# 5ChannelStepperDriver.net
KiCad netlist of a schematic drawn in EAGLE
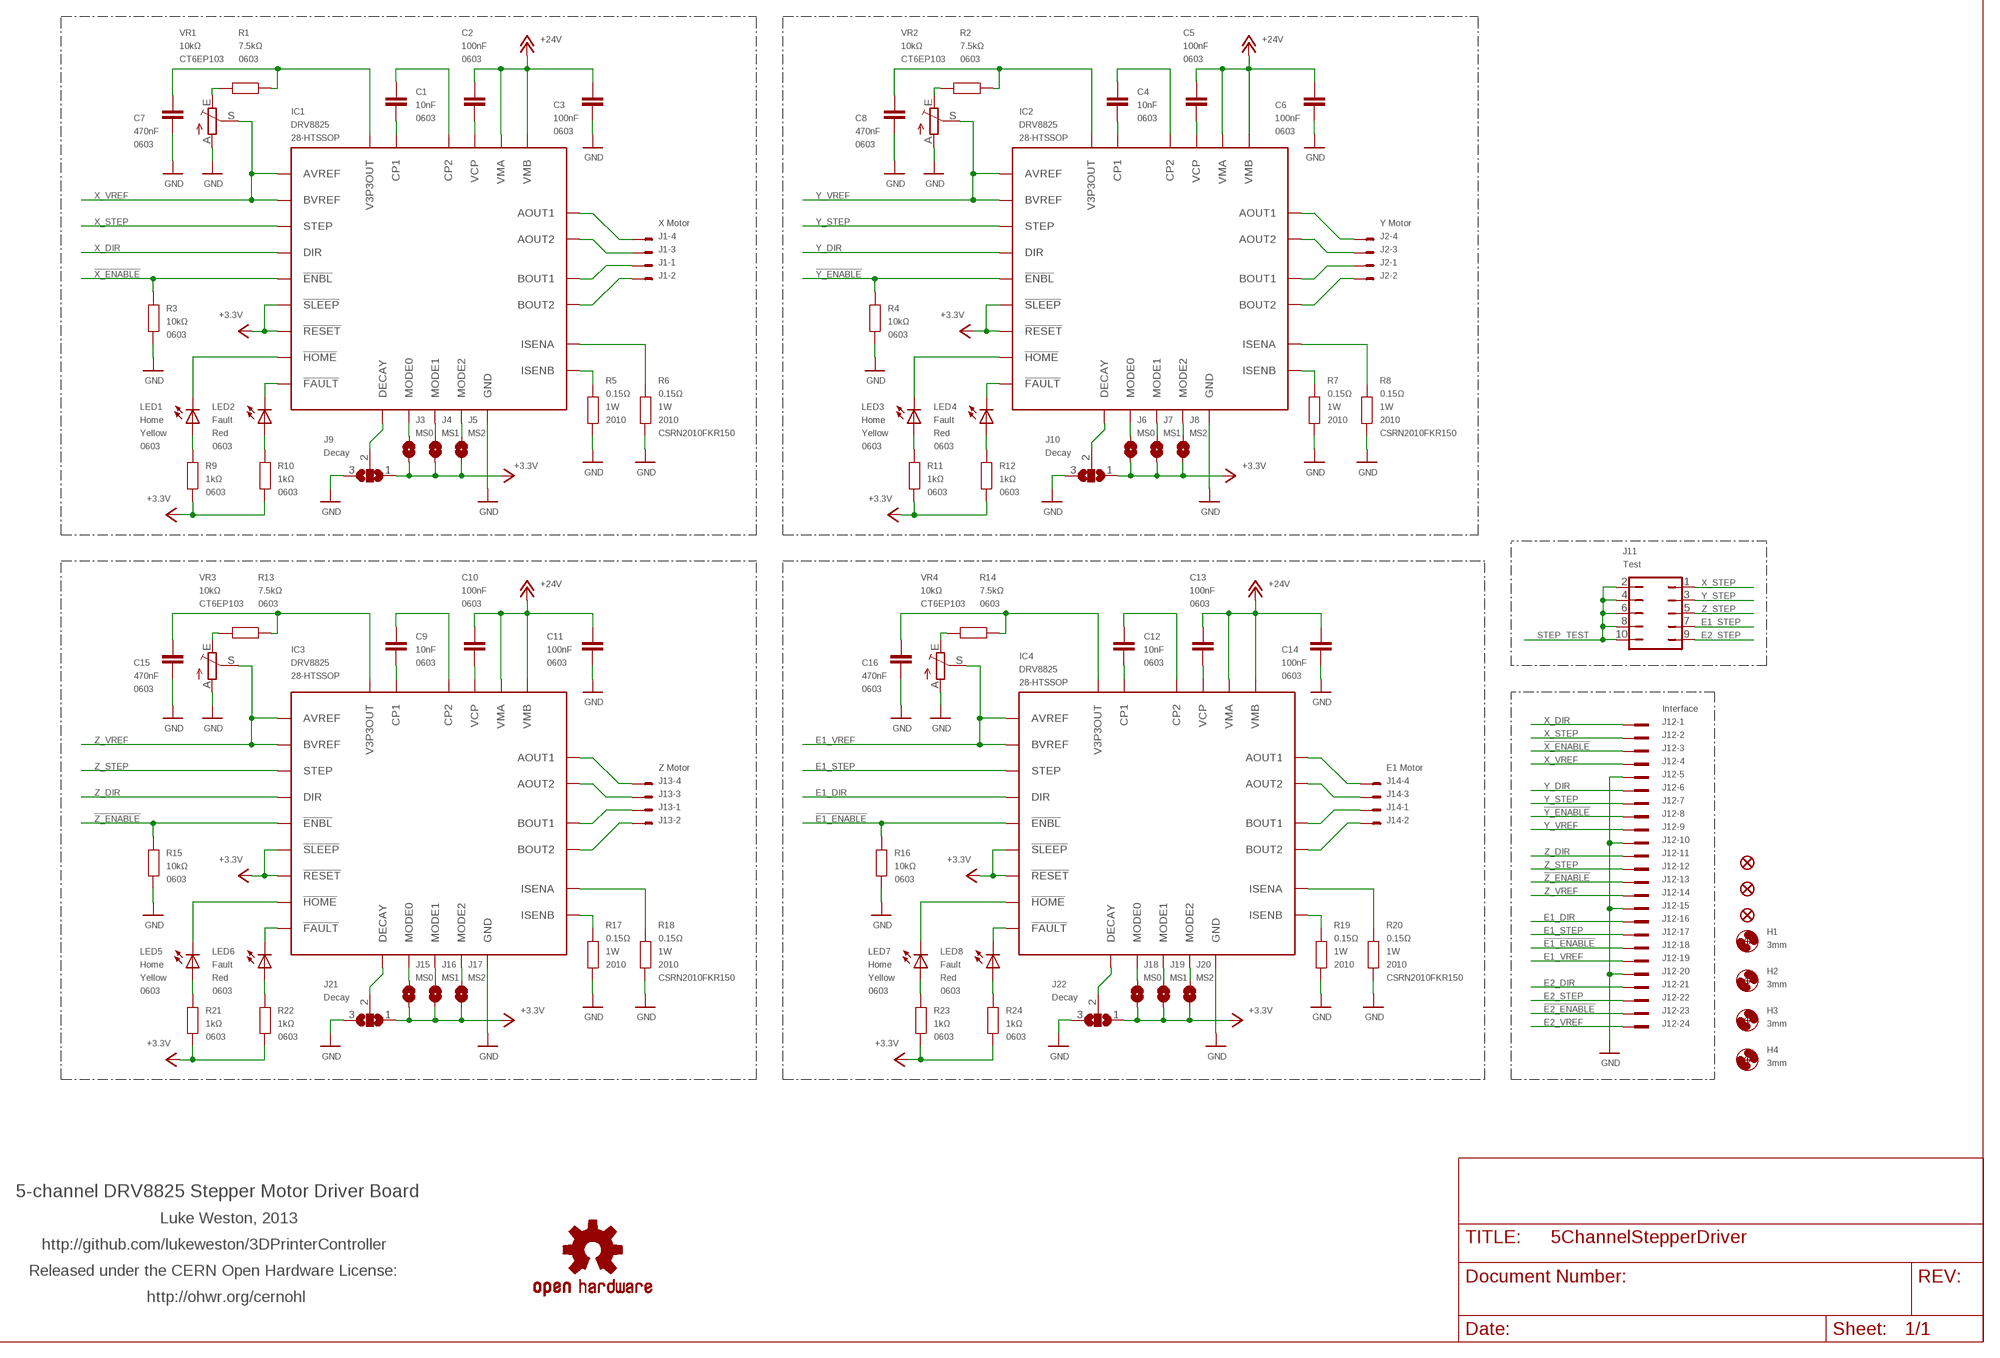
[diagram p0: schematic, sheet 1, part 1 of 3]
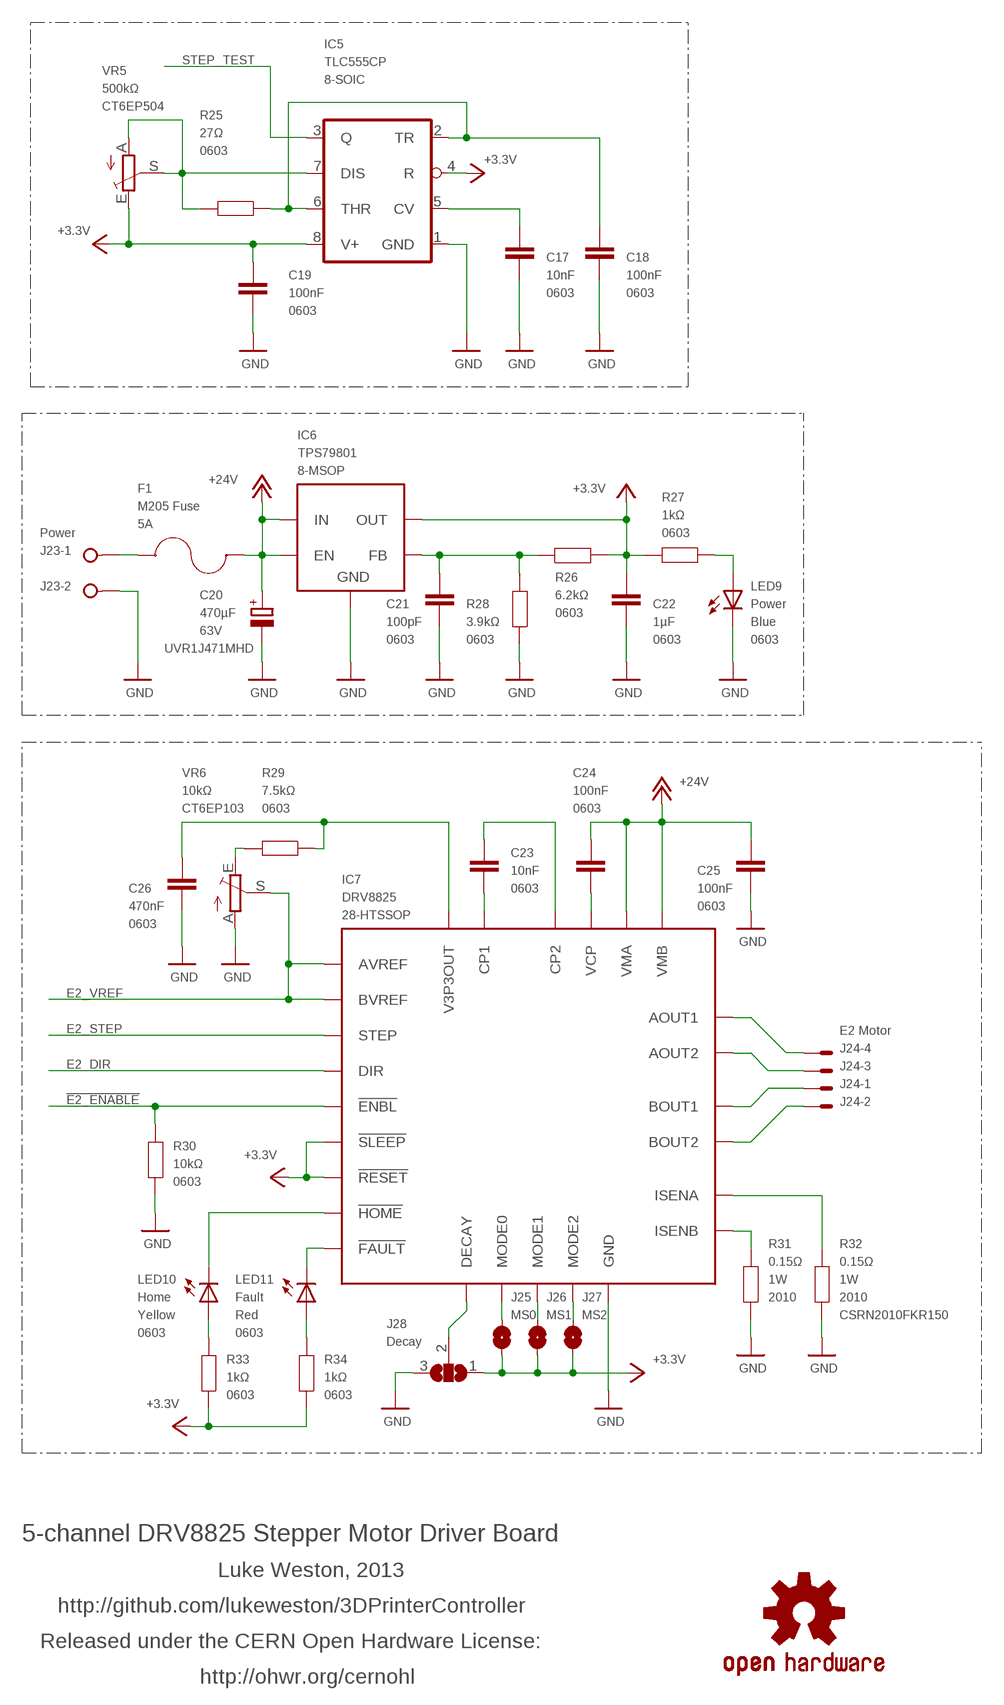
[diagram p1: schematic, sheet 1, part 2 of 3]
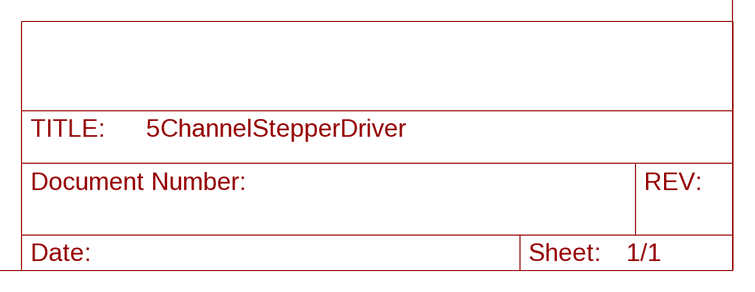
[diagram p2: schematic, sheet 1, part 3 of 3]

(export (version "E")
  (design (tool "Eeschema 10.0.6"))
  (components
    (comp (ref "C1")
      (value "10nF")
      (footprint "eagle-import:0603")
      (fields (field (name "PACKAGE") "0603"))
      (libsource (lib "eagle-import") (part "CAP0603"))
    )
    (comp (ref "C2")
      (value "100nF")
      (footprint "eagle-import:0603")
      (fields (field (name "PACKAGE") "0603"))
      (libsource (lib "eagle-import") (part "CAP0603"))
    )
    (comp (ref "C3")
      (value "100nF")
      (footprint "eagle-import:0603")
      (fields (field (name "PACKAGE") "0603"))
      (libsource (lib "eagle-import") (part "CAP0603"))
    )
    (comp (ref "C4")
      (value "10nF")
      (footprint "eagle-import:0603")
      (fields (field (name "PACKAGE") "0603"))
      (libsource (lib "eagle-import") (part "CAP0603"))
    )
    (comp (ref "C5")
      (value "100nF")
      (footprint "eagle-import:0603")
      (fields (field (name "PACKAGE") "0603"))
      (libsource (lib "eagle-import") (part "CAP0603"))
    )
    (comp (ref "C6")
      (value "100nF")
      (footprint "eagle-import:0603")
      (fields (field (name "PACKAGE") "0603"))
      (libsource (lib "eagle-import") (part "CAP0603"))
    )
    (comp (ref "C7")
      (value "470nF")
      (footprint "eagle-import:0603")
      (fields (field (name "PACKAGE") "0603"))
      (libsource (lib "eagle-import") (part "CAP0603"))
    )
    (comp (ref "C8")
      (value "470nF")
      (footprint "eagle-import:0603")
      (fields (field (name "PACKAGE") "0603"))
      (libsource (lib "eagle-import") (part "CAP0603"))
    )
    (comp (ref "C9")
      (value "10nF")
      (footprint "eagle-import:0603")
      (fields (field (name "PACKAGE") "0603"))
      (libsource (lib "eagle-import") (part "CAP0603"))
    )
    (comp (ref "C10")
      (value "100nF")
      (footprint "eagle-import:0603")
      (fields (field (name "PACKAGE") "0603"))
      (libsource (lib "eagle-import") (part "CAP0603"))
    )
    (comp (ref "C11")
      (value "100nF")
      (footprint "eagle-import:0603")
      (fields (field (name "PACKAGE") "0603"))
      (libsource (lib "eagle-import") (part "CAP0603"))
    )
    (comp (ref "C12")
      (value "10nF")
      (footprint "eagle-import:0603")
      (fields (field (name "PACKAGE") "0603"))
      (libsource (lib "eagle-import") (part "CAP0603"))
    )
    (comp (ref "C13")
      (value "100nF")
      (footprint "eagle-import:0603")
      (fields (field (name "PACKAGE") "0603"))
      (libsource (lib "eagle-import") (part "CAP0603"))
    )
    (comp (ref "C14")
      (value "100nF")
      (footprint "eagle-import:0603")
      (fields (field (name "PACKAGE") "0603"))
      (libsource (lib "eagle-import") (part "CAP0603"))
    )
    (comp (ref "C15")
      (value "470nF")
      (footprint "eagle-import:0603")
      (fields (field (name "PACKAGE") "0603"))
      (libsource (lib "eagle-import") (part "CAP0603"))
    )
    (comp (ref "C16")
      (value "470nF")
      (footprint "eagle-import:0603")
      (fields (field (name "PACKAGE") "0603"))
      (libsource (lib "eagle-import") (part "CAP0603"))
    )
    (comp (ref "C17")
      (value "10nF")
      (footprint "eagle-import:0603")
      (fields (field (name "PACKAGE") "0603"))
      (libsource (lib "eagle-import") (part "CAP0603"))
    )
    (comp (ref "C18")
      (value "100nF")
      (footprint "eagle-import:0603")
      (fields (field (name "PACKAGE") "0603"))
      (libsource (lib "eagle-import") (part "CAP0603"))
    )
    (comp (ref "C19")
      (value "100nF")
      (footprint "eagle-import:0603")
      (fields (field (name "PACKAGE") "0603"))
      (libsource (lib "eagle-import") (part "CAP0603"))
    )
    (comp (ref "C20")
      (value "470µF")
      (footprint "eagle-import:E5-13")
      (fields (field (name "SKU") "UVR1J471MHD") (field (name "VOLTAGE") "63V"))
      (libsource (lib "eagle-import") (part "CPOL-EUE5-13"))
    )
    (comp (ref "C21")
      (value "100pF")
      (footprint "eagle-import:0603")
      (fields (field (name "PACKAGE") "0603"))
      (libsource (lib "eagle-import") (part "CAP0603"))
    )
    (comp (ref "C22")
      (value "1µF")
      (footprint "eagle-import:0603")
      (fields (field (name "PACKAGE") "0603"))
      (libsource (lib "eagle-import") (part "CAP0603"))
    )
    (comp (ref "C23")
      (value "10nF")
      (footprint "eagle-import:0603")
      (fields (field (name "PACKAGE") "0603"))
      (libsource (lib "eagle-import") (part "CAP0603"))
    )
    (comp (ref "C24")
      (value "100nF")
      (footprint "eagle-import:0603")
      (fields (field (name "PACKAGE") "0603"))
      (libsource (lib "eagle-import") (part "CAP0603"))
    )
    (comp (ref "C25")
      (value "100nF")
      (footprint "eagle-import:0603")
      (fields (field (name "PACKAGE") "0603"))
      (libsource (lib "eagle-import") (part "CAP0603"))
    )
    (comp (ref "C26")
      (value "470nF")
      (footprint "eagle-import:0603")
      (fields (field (name "PACKAGE") "0603"))
      (libsource (lib "eagle-import") (part "CAP0603"))
    )
    (comp (ref "F1")
      (value "M205 Fuse")
      (footprint "eagle-import:FUSECLIP-FC211")
      (fields (field (name "VALUE2") "5A"))
      (libsource (lib "eagle-import") (part "FUSE-M205"))
    )
    (comp (ref "H1")
      (value "3mm")
      (footprint "eagle-import:3,0")
      (libsource (lib "eagle-import") (part "MOUNT-HOLE3.0"))
    )
    (comp (ref "H2")
      (value "3mm")
      (footprint "eagle-import:3,0")
      (libsource (lib "eagle-import") (part "MOUNT-HOLE3.0"))
    )
    (comp (ref "H3")
      (value "3mm")
      (footprint "eagle-import:3,0")
      (libsource (lib "eagle-import") (part "MOUNT-HOLE3.0"))
    )
    (comp (ref "H4")
      (value "3mm")
      (footprint "eagle-import:3,0")
      (libsource (lib "eagle-import") (part "MOUNT-HOLE3.0"))
    )
    (comp (ref "IC1")
      (value "DRV8825")
      (footprint "eagle-import:R-PDSO-G28")
      (fields (field (name "PACKAGE") "28-HTSSOP"))
      (libsource (lib "eagle-import") (part "DRV8825"))
    )
    (comp (ref "IC2")
      (value "DRV8825")
      (footprint "eagle-import:R-PDSO-G28")
      (fields (field (name "PACKAGE") "28-HTSSOP"))
      (libsource (lib "eagle-import") (part "DRV8825"))
    )
    (comp (ref "IC3")
      (value "DRV8825")
      (footprint "eagle-import:R-PDSO-G28")
      (fields (field (name "PACKAGE") "28-HTSSOP"))
      (libsource (lib "eagle-import") (part "DRV8825"))
    )
    (comp (ref "IC4")
      (value "DRV8825")
      (footprint "eagle-import:R-PDSO-G28")
      (fields (field (name "PACKAGE") "28-HTSSOP"))
      (libsource (lib "eagle-import") (part "DRV8825"))
    )
    (comp (ref "IC5")
      (value "TLC555CP")
      (footprint "eagle-import:SO08")
      (fields (field (name "PACKAGE") "8-SOIC"))
      (libsource (lib "eagle-import") (part "555DLM"))
    )
    (comp (ref "IC6")
      (value "TPS79801")
      (footprint "eagle-import:R-PDSO-G8")
      (fields (field (name "PACKAGE") "8-MSOP"))
      (libsource (lib "eagle-import") (part "TPS79801"))
    )
    (comp (ref "IC7")
      (value "DRV8825")
      (footprint "eagle-import:R-PDSO-G28")
      (fields (field (name "PACKAGE") "28-HTSSOP"))
      (libsource (lib "eagle-import") (part "DRV8825"))
    )
    (comp (ref "J1")
      (value "X Motor")
      (footprint "eagle-import:7395-04")
      (libsource (lib "eagle-import") (part "22-?-0405-7048"))
    )
    (comp (ref "J2")
      (value "Y Motor")
      (footprint "eagle-import:7395-04")
      (libsource (lib "eagle-import") (part "22-?-0405-7048"))
    )
    (comp (ref "J3") (value "MS0") (footprint "eagle-import:SJ") (libsource (lib "eagle-import") (part "SJ")))
    (comp (ref "J4") (value "MS1") (footprint "eagle-import:SJ") (libsource (lib "eagle-import") (part "SJ")))
    (comp (ref "J5") (value "MS2") (footprint "eagle-import:SJ") (libsource (lib "eagle-import") (part "SJ")))
    (comp (ref "J6") (value "MS0") (footprint "eagle-import:SJ") (libsource (lib "eagle-import") (part "SJ")))
    (comp (ref "J7") (value "MS1") (footprint "eagle-import:SJ") (libsource (lib "eagle-import") (part "SJ")))
    (comp (ref "J8") (value "MS2") (footprint "eagle-import:SJ") (libsource (lib "eagle-import") (part "SJ")))
    (comp (ref "J9")
      (value "Decay")
      (footprint "eagle-import:SJ_2")
      (libsource (lib "eagle-import") (part "SJ2W"))
    )
    (comp (ref "J10")
      (value "Decay")
      (footprint "eagle-import:SJ_2")
      (libsource (lib "eagle-import") (part "SJ2W"))
    )
    (comp (ref "J11")
      (value "Test")
      (footprint "eagle-import:JP5Q")
      (libsource (lib "eagle-import") (part "JP5Q"))
    )
    (comp (ref "J12")
      (value "Interface")
      (footprint "eagle-import:PAK100_2500-24")
      (libsource (lib "eagle-import") (part "2524-"))
    )
    (comp (ref "J13")
      (value "Z Motor")
      (footprint "eagle-import:7395-04")
      (libsource (lib "eagle-import") (part "22-?-0405-7048"))
    )
    (comp (ref "J14")
      (value "E1 Motor")
      (footprint "eagle-import:7395-04")
      (libsource (lib "eagle-import") (part "22-?-0405-7048"))
    )
    (comp (ref "J15")
      (value "MS0")
      (footprint "eagle-import:SJ")
      (libsource (lib "eagle-import") (part "SJ"))
    )
    (comp (ref "J16")
      (value "MS1")
      (footprint "eagle-import:SJ")
      (libsource (lib "eagle-import") (part "SJ"))
    )
    (comp (ref "J17")
      (value "MS2")
      (footprint "eagle-import:SJ")
      (libsource (lib "eagle-import") (part "SJ"))
    )
    (comp (ref "J18")
      (value "MS0")
      (footprint "eagle-import:SJ")
      (libsource (lib "eagle-import") (part "SJ"))
    )
    (comp (ref "J19")
      (value "MS1")
      (footprint "eagle-import:SJ")
      (libsource (lib "eagle-import") (part "SJ"))
    )
    (comp (ref "J20")
      (value "MS2")
      (footprint "eagle-import:SJ")
      (libsource (lib "eagle-import") (part "SJ"))
    )
    (comp (ref "J21")
      (value "Decay")
      (footprint "eagle-import:SJ_2")
      (libsource (lib "eagle-import") (part "SJ2W"))
    )
    (comp (ref "J22")
      (value "Decay")
      (footprint "eagle-import:SJ_2")
      (libsource (lib "eagle-import") (part "SJ2W"))
    )
    (comp (ref "J23")
      (value "Power")
      (footprint "eagle-import:W237-132")
      (libsource (lib "eagle-import") (part "W237-02P"))
    )
    (comp (ref "J24")
      (value "E2 Motor")
      (footprint "eagle-import:7395-04")
      (libsource (lib "eagle-import") (part "22-?-0405-7048"))
    )
    (comp (ref "J25")
      (value "MS0")
      (footprint "eagle-import:SJ")
      (libsource (lib "eagle-import") (part "SJ"))
    )
    (comp (ref "J26")
      (value "MS1")
      (footprint "eagle-import:SJ")
      (libsource (lib "eagle-import") (part "SJ"))
    )
    (comp (ref "J27")
      (value "MS2")
      (footprint "eagle-import:SJ")
      (libsource (lib "eagle-import") (part "SJ"))
    )
    (comp (ref "J28")
      (value "Decay")
      (footprint "eagle-import:SJ_2")
      (libsource (lib "eagle-import") (part "SJ2W"))
    )
    (comp (ref "JP1")
      (value "FIDUCIAL1X2")
      (footprint "eagle-import:FIDUCIAL-1X2")
      (libsource (lib "eagle-import") (part "FIDUCIAL1X2"))
    )
    (comp (ref "JP2")
      (value "FIDUCIAL1X2")
      (footprint "eagle-import:FIDUCIAL-1X2")
      (libsource (lib "eagle-import") (part "FIDUCIAL1X2"))
    )
    (comp (ref "JP3")
      (value "FIDUCIAL1X2")
      (footprint "eagle-import:FIDUCIAL-1X2")
      (libsource (lib "eagle-import") (part "FIDUCIAL1X2"))
    )
    (comp (ref "LED1")
      (value "Home")
      (footprint "eagle-import:LED-0603")
      (fields (field (name "COLOR") "Yellow") (field (name "PACKAGE") "0603"))
      (libsource (lib "eagle-import") (part "LED0603"))
    )
    (comp (ref "LED2")
      (value "Fault")
      (footprint "eagle-import:LED-0603")
      (fields (field (name "COLOR") "Red") (field (name "PACKAGE") "0603"))
      (libsource (lib "eagle-import") (part "LED0603"))
    )
    (comp (ref "LED3")
      (value "Home")
      (footprint "eagle-import:LED-0603")
      (fields (field (name "COLOR") "Yellow") (field (name "PACKAGE") "0603"))
      (libsource (lib "eagle-import") (part "LED0603"))
    )
    (comp (ref "LED4")
      (value "Fault")
      (footprint "eagle-import:LED-0603")
      (fields (field (name "COLOR") "Red") (field (name "PACKAGE") "0603"))
      (libsource (lib "eagle-import") (part "LED0603"))
    )
    (comp (ref "LED5")
      (value "Home")
      (footprint "eagle-import:LED-0603")
      (fields (field (name "COLOR") "Yellow") (field (name "PACKAGE") "0603"))
      (libsource (lib "eagle-import") (part "LED0603"))
    )
    (comp (ref "LED6")
      (value "Fault")
      (footprint "eagle-import:LED-0603")
      (fields (field (name "COLOR") "Red") (field (name "PACKAGE") "0603"))
      (libsource (lib "eagle-import") (part "LED0603"))
    )
    (comp (ref "LED7")
      (value "Home")
      (footprint "eagle-import:LED-0603")
      (fields (field (name "COLOR") "Yellow") (field (name "PACKAGE") "0603"))
      (libsource (lib "eagle-import") (part "LED0603"))
    )
    (comp (ref "LED8")
      (value "Fault")
      (footprint "eagle-import:LED-0603")
      (fields (field (name "COLOR") "Red") (field (name "PACKAGE") "0603"))
      (libsource (lib "eagle-import") (part "LED0603"))
    )
    (comp (ref "LED9")
      (value "Power")
      (footprint "eagle-import:LED-0603")
      (fields (field (name "COLOR") "Blue") (field (name "PACKAGE") "0603"))
      (libsource (lib "eagle-import") (part "LED0603"))
    )
    (comp (ref "LED10")
      (value "Home")
      (footprint "eagle-import:LED-0603")
      (fields (field (name "COLOR") "Yellow") (field (name "PACKAGE") "0603"))
      (libsource (lib "eagle-import") (part "LED0603"))
    )
    (comp (ref "LED11")
      (value "Fault")
      (footprint "eagle-import:LED-0603")
      (fields (field (name "COLOR") "Red") (field (name "PACKAGE") "0603"))
      (libsource (lib "eagle-import") (part "LED0603"))
    )
    (comp (ref "R1")
      (value "7.5kΩ")
      (footprint "eagle-import:0603")
      (fields (field (name "PACKAGE") "0603"))
      (libsource (lib "eagle-import") (part "RESISTOR0603"))
    )
    (comp (ref "R2")
      (value "7.5kΩ")
      (footprint "eagle-import:0603")
      (fields (field (name "PACKAGE") "0603"))
      (libsource (lib "eagle-import") (part "RESISTOR0603"))
    )
    (comp (ref "R3")
      (value "10kΩ")
      (footprint "eagle-import:0603")
      (fields (field (name "PACKAGE") "0603"))
      (libsource (lib "eagle-import") (part "RESISTOR0603"))
    )
    (comp (ref "R4")
      (value "10kΩ")
      (footprint "eagle-import:0603")
      (fields (field (name "PACKAGE") "0603"))
      (libsource (lib "eagle-import") (part "RESISTOR0603"))
    )
    (comp (ref "R5")
      (value "0.15Ω")
      (footprint "eagle-import:R2010")
      (fields (field (name "PACKAGE") "2010") (field (name "POWER") "1W"))
      (libsource (lib "eagle-import") (part "RESISTOR2010"))
    )
    (comp (ref "R6")
      (value "0.15Ω")
      (footprint "eagle-import:R2010")
      (fields
        (field (name "ID") "CSRN2010FKR150")
        (field (name "PACKAGE") "2010")
        (field (name "POWER") "1W")
      )
      (libsource (lib "eagle-import") (part "RESISTOR2010"))
    )
    (comp (ref "R7")
      (value "0.15Ω")
      (footprint "eagle-import:R2010")
      (fields (field (name "PACKAGE") "2010") (field (name "POWER") "1W"))
      (libsource (lib "eagle-import") (part "RESISTOR2010"))
    )
    (comp (ref "R8")
      (value "0.15Ω")
      (footprint "eagle-import:R2010")
      (fields
        (field (name "ID") "CSRN2010FKR150")
        (field (name "PACKAGE") "2010")
        (field (name "POWER") "1W")
      )
      (libsource (lib "eagle-import") (part "RESISTOR2010"))
    )
    (comp (ref "R9")
      (value "1kΩ")
      (footprint "eagle-import:0603")
      (fields (field (name "PACKAGE") "0603"))
      (libsource (lib "eagle-import") (part "RESISTOR0603"))
    )
    (comp (ref "R10")
      (value "1kΩ")
      (footprint "eagle-import:0603")
      (fields (field (name "PACKAGE") "0603"))
      (libsource (lib "eagle-import") (part "RESISTOR0603"))
    )
    (comp (ref "R11")
      (value "1kΩ")
      (footprint "eagle-import:0603")
      (fields (field (name "PACKAGE") "0603"))
      (libsource (lib "eagle-import") (part "RESISTOR0603"))
    )
    (comp (ref "R12")
      (value "1kΩ")
      (footprint "eagle-import:0603")
      (fields (field (name "PACKAGE") "0603"))
      (libsource (lib "eagle-import") (part "RESISTOR0603"))
    )
    (comp (ref "R13")
      (value "7.5kΩ")
      (footprint "eagle-import:0603")
      (fields (field (name "PACKAGE") "0603"))
      (libsource (lib "eagle-import") (part "RESISTOR0603"))
    )
    (comp (ref "R14")
      (value "7.5kΩ")
      (footprint "eagle-import:0603")
      (fields (field (name "PACKAGE") "0603"))
      (libsource (lib "eagle-import") (part "RESISTOR0603"))
    )
    (comp (ref "R15")
      (value "10kΩ")
      (footprint "eagle-import:0603")
      (fields (field (name "PACKAGE") "0603"))
      (libsource (lib "eagle-import") (part "RESISTOR0603"))
    )
    (comp (ref "R16")
      (value "10kΩ")
      (footprint "eagle-import:0603")
      (fields (field (name "PACKAGE") "0603"))
      (libsource (lib "eagle-import") (part "RESISTOR0603"))
    )
    (comp (ref "R17")
      (value "0.15Ω")
      (footprint "eagle-import:R2010")
      (fields (field (name "PACKAGE") "2010") (field (name "POWER") "1W"))
      (libsource (lib "eagle-import") (part "RESISTOR2010"))
    )
    (comp (ref "R18")
      (value "0.15Ω")
      (footprint "eagle-import:R2010")
      (fields
        (field (name "ID") "CSRN2010FKR150")
        (field (name "PACKAGE") "2010")
        (field (name "POWER") "1W")
      )
      (libsource (lib "eagle-import") (part "RESISTOR2010"))
    )
    (comp (ref "R19")
      (value "0.15Ω")
      (footprint "eagle-import:R2010")
      (fields (field (name "PACKAGE") "2010") (field (name "POWER") "1W"))
      (libsource (lib "eagle-import") (part "RESISTOR2010"))
    )
    (comp (ref "R20")
      (value "0.15Ω")
      (footprint "eagle-import:R2010")
      (fields
        (field (name "ID") "CSRN2010FKR150")
        (field (name "PACKAGE") "2010")
        (field (name "POWER") "1W")
      )
      (libsource (lib "eagle-import") (part "RESISTOR2010"))
    )
    (comp (ref "R21")
      (value "1kΩ")
      (footprint "eagle-import:0603")
      (fields (field (name "PACKAGE") "0603"))
      (libsource (lib "eagle-import") (part "RESISTOR0603"))
    )
    (comp (ref "R22")
      (value "1kΩ")
      (footprint "eagle-import:0603")
      (fields (field (name "PACKAGE") "0603"))
      (libsource (lib "eagle-import") (part "RESISTOR0603"))
    )
    (comp (ref "R23")
      (value "1kΩ")
      (footprint "eagle-import:0603")
      (fields (field (name "PACKAGE") "0603"))
      (libsource (lib "eagle-import") (part "RESISTOR0603"))
    )
    (comp (ref "R24")
      (value "1kΩ")
      (footprint "eagle-import:0603")
      (fields (field (name "PACKAGE") "0603"))
      (libsource (lib "eagle-import") (part "RESISTOR0603"))
    )
    (comp (ref "R25")
      (value "27Ω")
      (footprint "eagle-import:0603")
      (fields (field (name "PACKAGE") "0603"))
      (libsource (lib "eagle-import") (part "RESISTOR0603"))
    )
    (comp (ref "R26")
      (value "6.2kΩ")
      (footprint "eagle-import:0603")
      (fields (field (name "PACKAGE") "0603"))
      (libsource (lib "eagle-import") (part "RESISTOR0603"))
    )
    (comp (ref "R27")
      (value "1kΩ")
      (footprint "eagle-import:0603")
      (fields (field (name "PACKAGE") "0603"))
      (libsource (lib "eagle-import") (part "RESISTOR0603"))
    )
    (comp (ref "R28")
      (value "3.9kΩ")
      (footprint "eagle-import:0603")
      (fields (field (name "PACKAGE") "0603"))
      (libsource (lib "eagle-import") (part "RESISTOR0603"))
    )
    (comp (ref "R29")
      (value "7.5kΩ")
      (footprint "eagle-import:0603")
      (fields (field (name "PACKAGE") "0603"))
      (libsource (lib "eagle-import") (part "RESISTOR0603"))
    )
    (comp (ref "R30")
      (value "10kΩ")
      (footprint "eagle-import:0603")
      (fields (field (name "PACKAGE") "0603"))
      (libsource (lib "eagle-import") (part "RESISTOR0603"))
    )
    (comp (ref "R31")
      (value "0.15Ω")
      (footprint "eagle-import:R2010")
      (fields (field (name "PACKAGE") "2010") (field (name "POWER") "1W"))
      (libsource (lib "eagle-import") (part "RESISTOR2010"))
    )
    (comp (ref "R32")
      (value "0.15Ω")
      (footprint "eagle-import:R2010")
      (fields
        (field (name "ID") "CSRN2010FKR150")
        (field (name "PACKAGE") "2010")
        (field (name "POWER") "1W")
      )
      (libsource (lib "eagle-import") (part "RESISTOR2010"))
    )
    (comp (ref "R33")
      (value "1kΩ")
      (footprint "eagle-import:0603")
      (fields (field (name "PACKAGE") "0603"))
      (libsource (lib "eagle-import") (part "RESISTOR0603"))
    )
    (comp (ref "R34")
      (value "1kΩ")
      (footprint "eagle-import:0603")
      (fields (field (name "PACKAGE") "0603"))
      (libsource (lib "eagle-import") (part "RESISTOR0603"))
    )
    (comp (ref "SY1")
      (value "OSHW-LOGOS")
      (footprint "eagle-import:OSHW-LOGO-S")
      (libsource (lib "eagle-import") (part "OSHW-LOGOS"))
    )
    (comp (ref "SY2")
      (value "OSHW-LOGOS")
      (footprint "eagle-import:OSHW-LOGO-S")
      (libsource (lib "eagle-import") (part "OSHW-LOGOS"))
    )
    (comp (ref "VR1")
      (value "10kΩ")
      (footprint "eagle-import:CT6")
      (fields (field (name "ID") "CT6EP103"))
      (libsource (lib "eagle-import") (part "TRIM_EU-CT6"))
    )
    (comp (ref "VR2")
      (value "10kΩ")
      (footprint "eagle-import:CT6")
      (fields (field (name "ID") "CT6EP103"))
      (libsource (lib "eagle-import") (part "TRIM_EU-CT6"))
    )
    (comp (ref "VR3")
      (value "10kΩ")
      (footprint "eagle-import:CT6")
      (fields (field (name "ID") "CT6EP103"))
      (libsource (lib "eagle-import") (part "TRIM_EU-CT6"))
    )
    (comp (ref "VR4")
      (value "10kΩ")
      (footprint "eagle-import:CT6")
      (fields (field (name "ID") "CT6EP103"))
      (libsource (lib "eagle-import") (part "TRIM_EU-CT6"))
    )
    (comp (ref "VR5")
      (value "500kΩ")
      (footprint "eagle-import:CT6")
      (fields (field (name "ID") "CT6EP504"))
      (libsource (lib "eagle-import") (part "TRIM_EU-CT6"))
    )
    (comp (ref "VR6")
      (value "10kΩ")
      (footprint "eagle-import:CT6")
      (fields (field (name "ID") "CT6EP103"))
      (libsource (lib "eagle-import") (part "TRIM_EU-CT6"))
    )
  )
  (nets
    (net (code "1") (name "+3.3V") (class "Default")
      (node (ref "C19") (pin "1") (pinfunction "1_1") (pintype "passive"))
      (node (ref "C22") (pin "1") (pinfunction "1_1") (pintype "passive"))
      (node (ref "IC1") (pin "16") (pinfunction "~{RESET}_16") (pintype "bidirectional"))
      (node (ref "IC1") (pin "17") (pinfunction "~{SLEEP}_17") (pintype "bidirectional"))
      (node (ref "IC2") (pin "16") (pinfunction "~{RESET}_16") (pintype "bidirectional"))
      (node (ref "IC2") (pin "17") (pinfunction "~{SLEEP}_17") (pintype "bidirectional"))
      (node (ref "IC3") (pin "16") (pinfunction "~{RESET}_16") (pintype "bidirectional"))
      (node (ref "IC3") (pin "17") (pinfunction "~{SLEEP}_17") (pintype "bidirectional"))
      (node (ref "IC4") (pin "16") (pinfunction "~{RESET}_16") (pintype "bidirectional"))
      (node (ref "IC4") (pin "17") (pinfunction "~{SLEEP}_17") (pintype "bidirectional"))
      (node (ref "IC5") (pin "4") (pinfunction "R_4") (pintype "input"))
      (node (ref "IC5") (pin "8") (pinfunction "V+_8") (pintype "power_in"))
      (node (ref "IC6") (pin "1") (pinfunction "OUT_1") (pintype "bidirectional"))
      (node (ref "IC7") (pin "16") (pinfunction "~{RESET}_16") (pintype "bidirectional"))
      (node (ref "IC7") (pin "17") (pinfunction "~{SLEEP}_17") (pintype "bidirectional"))
      (node (ref "J10") (pin "1") (pinfunction "1_1") (pintype "passive"))
      (node (ref "J15") (pin "1") (pinfunction "1_1") (pintype "passive"))
      (node (ref "J16") (pin "1") (pinfunction "1_1") (pintype "passive"))
      (node (ref "J17") (pin "1") (pinfunction "1_1") (pintype "passive"))
      (node (ref "J18") (pin "1") (pinfunction "1_1") (pintype "passive"))
      (node (ref "J19") (pin "1") (pinfunction "1_1") (pintype "passive"))
      (node (ref "J20") (pin "1") (pinfunction "1_1") (pintype "passive"))
      (node (ref "J21") (pin "1") (pinfunction "1_1") (pintype "passive"))
      (node (ref "J22") (pin "1") (pinfunction "1_1") (pintype "passive"))
      (node (ref "J25") (pin "1") (pinfunction "1_1") (pintype "passive"))
      (node (ref "J26") (pin "1") (pinfunction "1_1") (pintype "passive"))
      (node (ref "J27") (pin "1") (pinfunction "1_1") (pintype "passive"))
      (node (ref "J28") (pin "1") (pinfunction "1_1") (pintype "passive"))
      (node (ref "J3") (pin "1") (pinfunction "1_1") (pintype "passive"))
      (node (ref "J4") (pin "1") (pinfunction "1_1") (pintype "passive"))
      (node (ref "J5") (pin "1") (pinfunction "1_1") (pintype "passive"))
      (node (ref "J6") (pin "1") (pinfunction "1_1") (pintype "passive"))
      (node (ref "J7") (pin "1") (pinfunction "1_1") (pintype "passive"))
      (node (ref "J8") (pin "1") (pinfunction "1_1") (pintype "passive"))
      (node (ref "J9") (pin "1") (pinfunction "1_1") (pintype "passive"))
      (node (ref "R10") (pin "2") (pinfunction "2_2") (pintype "passive"))
      (node (ref "R11") (pin "2") (pinfunction "2_2") (pintype "passive"))
      (node (ref "R12") (pin "2") (pinfunction "2_2") (pintype "passive"))
      (node (ref "R21") (pin "2") (pinfunction "2_2") (pintype "passive"))
      (node (ref "R22") (pin "2") (pinfunction "2_2") (pintype "passive"))
      (node (ref "R23") (pin "2") (pinfunction "2_2") (pintype "passive"))
      (node (ref "R24") (pin "2") (pinfunction "2_2") (pintype "passive"))
      (node (ref "R26") (pin "2") (pinfunction "2_2") (pintype "passive"))
      (node (ref "R27") (pin "2") (pinfunction "2_2") (pintype "passive"))
      (node (ref "R33") (pin "2") (pinfunction "2_2") (pintype "passive"))
      (node (ref "R34") (pin "2") (pinfunction "2_2") (pintype "passive"))
      (node (ref "R9") (pin "2") (pinfunction "2_2") (pintype "passive"))
      (node (ref "VR5") (pin "E") (pinfunction "E_E") (pintype "passive"))
    )
    (net (code "2") (name "+24V") (class "Default")
      (node (ref "C10") (pin "1") (pinfunction "1_1") (pintype "passive"))
      (node (ref "C11") (pin "1") (pinfunction "1_1") (pintype "passive"))
      (node (ref "C13") (pin "1") (pinfunction "1_1") (pintype "passive"))
      (node (ref "C14") (pin "1") (pinfunction "1_1") (pintype "passive"))
      (node (ref "C2") (pin "1") (pinfunction "1_1") (pintype "passive"))
      (node (ref "C20") (pin "+") (pinfunction "+_+") (pintype "passive"))
      (node (ref "C24") (pin "1") (pinfunction "1_1") (pintype "passive"))
      (node (ref "C25") (pin "1") (pinfunction "1_1") (pintype "passive"))
      (node (ref "C3") (pin "1") (pinfunction "1_1") (pintype "passive"))
      (node (ref "C5") (pin "1") (pinfunction "1_1") (pintype "passive"))
      (node (ref "C6") (pin "1") (pinfunction "1_1") (pintype "passive"))
      (node (ref "F1") (pin "3") (pinfunction "2_3") (pintype "bidirectional"))
      (node (ref "F1") (pin "4") (pinfunction "2_4") (pintype "bidirectional"))
      (node (ref "IC1") (pin "11") (pinfunction "VMB_11") (pintype "bidirectional"))
      (node (ref "IC1") (pin "4") (pinfunction "VMA_4") (pintype "bidirectional"))
      (node (ref "IC2") (pin "11") (pinfunction "VMB_11") (pintype "bidirectional"))
      (node (ref "IC2") (pin "4") (pinfunction "VMA_4") (pintype "bidirectional"))
      (node (ref "IC3") (pin "11") (pinfunction "VMB_11") (pintype "bidirectional"))
      (node (ref "IC3") (pin "4") (pinfunction "VMA_4") (pintype "bidirectional"))
      (node (ref "IC4") (pin "11") (pinfunction "VMB_11") (pintype "bidirectional"))
      (node (ref "IC4") (pin "4") (pinfunction "VMA_4") (pintype "bidirectional"))
      (node (ref "IC6") (pin "5") (pinfunction "EN_5") (pintype "bidirectional"))
      (node (ref "IC6") (pin "8") (pinfunction "IN_8") (pintype "bidirectional"))
      (node (ref "IC7") (pin "11") (pinfunction "VMB_11") (pintype "bidirectional"))
      (node (ref "IC7") (pin "4") (pinfunction "VMA_4") (pintype "bidirectional"))
    )
    (net (code "3") (name "/E1_DIR") (class "Default")
      (node (ref "IC4") (pin "20") (pinfunction "DIR_20") (pintype "bidirectional"))
      (node (ref "J12") (pin "16") (pinfunction "KL_16") (pintype "passive"))
    )
    (net (code "4") (name "/E1_STEP") (class "Default")
      (node (ref "IC4") (pin "22") (pinfunction "STEP_22") (pintype "bidirectional"))
      (node (ref "J11") (pin "7") (pinfunction "7_7") (pintype "passive"))
      (node (ref "J12") (pin "17") (pinfunction "KL_17") (pintype "passive"))
    )
    (net (code "5") (name "/E1_VREF") (class "Default")
      (node (ref "IC4") (pin "12") (pinfunction "AVREF_12") (pintype "bidirectional"))
      (node (ref "IC4") (pin "13") (pinfunction "BVREF_13") (pintype "bidirectional"))
      (node (ref "J12") (pin "19") (pinfunction "KL_19") (pintype "passive"))
      (node (ref "VR4") (pin "S") (pinfunction "S_S") (pintype "passive"))
    )
    (net (code "6") (name "/E2_DIR") (class "Default")
      (node (ref "IC7") (pin "20") (pinfunction "DIR_20") (pintype "bidirectional"))
      (node (ref "J12") (pin "21") (pinfunction "KL_21") (pintype "passive"))
    )
    (net (code "7") (name "/E2_STEP") (class "Default")
      (node (ref "IC7") (pin "22") (pinfunction "STEP_22") (pintype "bidirectional"))
      (node (ref "J11") (pin "9") (pinfunction "9_9") (pintype "passive"))
      (node (ref "J12") (pin "22") (pinfunction "KL_22") (pintype "passive"))
    )
    (net (code "8") (name "/E2_VREF") (class "Default")
      (node (ref "IC7") (pin "12") (pinfunction "AVREF_12") (pintype "bidirectional"))
      (node (ref "IC7") (pin "13") (pinfunction "BVREF_13") (pintype "bidirectional"))
      (node (ref "J12") (pin "24") (pinfunction "KL_24") (pintype "passive"))
      (node (ref "VR6") (pin "S") (pinfunction "S_S") (pintype "passive"))
    )
    (net (code "9") (name "/STEP_TEST") (class "Default")
      (node (ref "IC5") (pin "3") (pinfunction "Q_3") (pintype "output"))
      (node (ref "J11") (pin "10") (pinfunction "10_10") (pintype "passive"))
      (node (ref "J11") (pin "2") (pinfunction "2_2") (pintype "passive"))
      (node (ref "J11") (pin "4") (pinfunction "4_4") (pintype "passive"))
      (node (ref "J11") (pin "6") (pinfunction "6_6") (pintype "passive"))
      (node (ref "J11") (pin "8") (pinfunction "8_8") (pintype "passive"))
    )
    (net (code "10") (name "/X_DIR") (class "Default")
      (node (ref "IC1") (pin "20") (pinfunction "DIR_20") (pintype "bidirectional"))
      (node (ref "J12") (pin "1") (pinfunction "KL_1") (pintype "passive"))
    )
    (net (code "11") (name "/X_STEP") (class "Default")
      (node (ref "IC1") (pin "22") (pinfunction "STEP_22") (pintype "bidirectional"))
      (node (ref "J11") (pin "1") (pinfunction "1_1") (pintype "passive"))
      (node (ref "J12") (pin "2") (pinfunction "KL_2") (pintype "passive"))
    )
    (net (code "12") (name "/X_VREF") (class "Default")
      (node (ref "IC1") (pin "12") (pinfunction "AVREF_12") (pintype "bidirectional"))
      (node (ref "IC1") (pin "13") (pinfunction "BVREF_13") (pintype "bidirectional"))
      (node (ref "J12") (pin "4") (pinfunction "KL_4") (pintype "passive"))
      (node (ref "VR1") (pin "S") (pinfunction "S_S") (pintype "passive"))
    )
    (net (code "13") (name "/Y_DIR") (class "Default")
      (node (ref "IC2") (pin "20") (pinfunction "DIR_20") (pintype "bidirectional"))
      (node (ref "J12") (pin "6") (pinfunction "KL_6") (pintype "passive"))
    )
    (net (code "14") (name "/Y_STEP") (class "Default")
      (node (ref "IC2") (pin "22") (pinfunction "STEP_22") (pintype "bidirectional"))
      (node (ref "J11") (pin "3") (pinfunction "3_3") (pintype "passive"))
      (node (ref "J12") (pin "7") (pinfunction "KL_7") (pintype "passive"))
    )
    (net (code "15") (name "/Y_VREF") (class "Default")
      (node (ref "IC2") (pin "12") (pinfunction "AVREF_12") (pintype "bidirectional"))
      (node (ref "IC2") (pin "13") (pinfunction "BVREF_13") (pintype "bidirectional"))
      (node (ref "J12") (pin "9") (pinfunction "KL_9") (pintype "passive"))
      (node (ref "VR2") (pin "S") (pinfunction "S_S") (pintype "passive"))
    )
    (net (code "16") (name "/Z_DIR") (class "Default")
      (node (ref "IC3") (pin "20") (pinfunction "DIR_20") (pintype "bidirectional"))
      (node (ref "J12") (pin "11") (pinfunction "KL_11") (pintype "passive"))
    )
    (net (code "17") (name "/Z_STEP") (class "Default")
      (node (ref "IC3") (pin "22") (pinfunction "STEP_22") (pintype "bidirectional"))
      (node (ref "J11") (pin "5") (pinfunction "5_5") (pintype "passive"))
      (node (ref "J12") (pin "12") (pinfunction "KL_12") (pintype "passive"))
    )
    (net (code "18") (name "/Z_VREF") (class "Default")
      (node (ref "IC3") (pin "12") (pinfunction "AVREF_12") (pintype "bidirectional"))
      (node (ref "IC3") (pin "13") (pinfunction "BVREF_13") (pintype "bidirectional"))
      (node (ref "J12") (pin "14") (pinfunction "KL_14") (pintype "passive"))
      (node (ref "VR3") (pin "S") (pinfunction "S_S") (pintype "passive"))
    )
    (net (code "19") (name "/~{E1_ENABLE}") (class "Default")
      (node (ref "IC4") (pin "21") (pinfunction "~{ENBL}_21") (pintype "bidirectional"))
      (node (ref "J12") (pin "18") (pinfunction "KL_18") (pintype "passive"))
      (node (ref "R16") (pin "1") (pinfunction "1_1") (pintype "passive"))
    )
    (net (code "20") (name "/~{E2_ENABLE}") (class "Default")
      (node (ref "IC7") (pin "21") (pinfunction "~{ENBL}_21") (pintype "bidirectional"))
      (node (ref "J12") (pin "23") (pinfunction "KL_23") (pintype "passive"))
      (node (ref "R30") (pin "1") (pinfunction "1_1") (pintype "passive"))
    )
    (net (code "21") (name "/~{X_ENABLE}") (class "Default")
      (node (ref "IC1") (pin "21") (pinfunction "~{ENBL}_21") (pintype "bidirectional"))
      (node (ref "J12") (pin "3") (pinfunction "KL_3") (pintype "passive"))
      (node (ref "R3") (pin "1") (pinfunction "1_1") (pintype "passive"))
    )
    (net (code "22") (name "/~{Y_ENABLE}") (class "Default")
      (node (ref "IC2") (pin "21") (pinfunction "~{ENBL}_21") (pintype "bidirectional"))
      (node (ref "J12") (pin "8") (pinfunction "KL_8") (pintype "passive"))
      (node (ref "R4") (pin "1") (pinfunction "1_1") (pintype "passive"))
    )
    (net (code "23") (name "/~{Z_ENABLE}") (class "Default")
      (node (ref "IC3") (pin "21") (pinfunction "~{ENBL}_21") (pintype "bidirectional"))
      (node (ref "J12") (pin "13") (pinfunction "KL_13") (pintype "passive"))
      (node (ref "R15") (pin "1") (pinfunction "1_1") (pintype "passive"))
    )
    (net (code "24") (name "GND") (class "Default")
      (node (ref "C11") (pin "2") (pinfunction "2_2") (pintype "passive"))
      (node (ref "C14") (pin "2") (pinfunction "2_2") (pintype "passive"))
      (node (ref "C15") (pin "2") (pinfunction "2_2") (pintype "passive"))
      (node (ref "C16") (pin "2") (pinfunction "2_2") (pintype "passive"))
      (node (ref "C17") (pin "2") (pinfunction "2_2") (pintype "passive"))
      (node (ref "C18") (pin "2") (pinfunction "2_2") (pintype "passive"))
      (node (ref "C19") (pin "2") (pinfunction "2_2") (pintype "passive"))
      (node (ref "C20") (pin "-") (pinfunction "-_-") (pintype "passive"))
      (node (ref "C21") (pin "2") (pinfunction "2_2") (pintype "passive"))
      (node (ref "C22") (pin "2") (pinfunction "2_2") (pintype "passive"))
      (node (ref "C25") (pin "2") (pinfunction "2_2") (pintype "passive"))
      (node (ref "C26") (pin "2") (pinfunction "2_2") (pintype "passive"))
      (node (ref "C3") (pin "2") (pinfunction "2_2") (pintype "passive"))
      (node (ref "C6") (pin "2") (pinfunction "2_2") (pintype "passive"))
      (node (ref "C7") (pin "2") (pinfunction "2_2") (pintype "passive"))
      (node (ref "C8") (pin "2") (pinfunction "2_2") (pintype "passive"))
      (node (ref "IC1") (pin "14") (pinfunction "GND_14") (pintype "bidirectional"))
      (node (ref "IC1") (pin "28") (pinfunction "GND_28") (pintype "bidirectional"))
      (node (ref "IC1") (pin "PAD") (pinfunction "GND_PAD") (pintype "bidirectional"))
      (node (ref "IC2") (pin "14") (pinfunction "GND_14") (pintype "bidirectional"))
      (node (ref "IC2") (pin "28") (pinfunction "GND_28") (pintype "bidirectional"))
      (node (ref "IC2") (pin "PAD") (pinfunction "GND_PAD") (pintype "bidirectional"))
      (node (ref "IC3") (pin "14") (pinfunction "GND_14") (pintype "bidirectional"))
      (node (ref "IC3") (pin "28") (pinfunction "GND_28") (pintype "bidirectional"))
      (node (ref "IC3") (pin "PAD") (pinfunction "GND_PAD") (pintype "bidirectional"))
      (node (ref "IC4") (pin "14") (pinfunction "GND_14") (pintype "bidirectional"))
      (node (ref "IC4") (pin "28") (pinfunction "GND_28") (pintype "bidirectional"))
      (node (ref "IC4") (pin "PAD") (pinfunction "GND_PAD") (pintype "bidirectional"))
      (node (ref "IC5") (pin "1") (pinfunction "GND_1") (pintype "power_in"))
      (node (ref "IC6") (pin "4") (pinfunction "GND_4") (pintype "bidirectional"))
      (node (ref "IC6") (pin "PAD") (pinfunction "GND_PAD") (pintype "bidirectional"))
      (node (ref "IC7") (pin "14") (pinfunction "GND_14") (pintype "bidirectional"))
      (node (ref "IC7") (pin "28") (pinfunction "GND_28") (pintype "bidirectional"))
      (node (ref "IC7") (pin "PAD") (pinfunction "GND_PAD") (pintype "bidirectional"))
      (node (ref "J10") (pin "3") (pinfunction "3_3") (pintype "passive"))
      (node (ref "J12") (pin "10") (pinfunction "KL_10") (pintype "passive"))
      (node (ref "J12") (pin "15") (pinfunction "KL_15") (pintype "passive"))
      (node (ref "J12") (pin "20") (pinfunction "KL_20") (pintype "passive"))
      (node (ref "J12") (pin "5") (pinfunction "KL_5") (pintype "passive"))
      (node (ref "J21") (pin "3") (pinfunction "3_3") (pintype "passive"))
      (node (ref "J22") (pin "3") (pinfunction "3_3") (pintype "passive"))
      (node (ref "J23") (pin "2") (pinfunction "KL_2") (pintype "passive"))
      (node (ref "J28") (pin "3") (pinfunction "3_3") (pintype "passive"))
      (node (ref "J9") (pin "3") (pinfunction "3_3") (pintype "passive"))
      (node (ref "LED9") (pin "C") (pinfunction "C_C") (pintype "passive"))
      (node (ref "R15") (pin "2") (pinfunction "2_2") (pintype "passive"))
      (node (ref "R16") (pin "2") (pinfunction "2_2") (pintype "passive"))
      (node (ref "R17") (pin "2") (pinfunction "2_2") (pintype "passive"))
      (node (ref "R18") (pin "2") (pinfunction "2_2") (pintype "passive"))
      (node (ref "R19") (pin "2") (pinfunction "2_2") (pintype "passive"))
      (node (ref "R20") (pin "2") (pinfunction "2_2") (pintype "passive"))
      (node (ref "R28") (pin "2") (pinfunction "2_2") (pintype "passive"))
      (node (ref "R3") (pin "2") (pinfunction "2_2") (pintype "passive"))
      (node (ref "R30") (pin "2") (pinfunction "2_2") (pintype "passive"))
      (node (ref "R31") (pin "2") (pinfunction "2_2") (pintype "passive"))
      (node (ref "R32") (pin "2") (pinfunction "2_2") (pintype "passive"))
      (node (ref "R4") (pin "2") (pinfunction "2_2") (pintype "passive"))
      (node (ref "R5") (pin "2") (pinfunction "2_2") (pintype "passive"))
      (node (ref "R6") (pin "2") (pinfunction "2_2") (pintype "passive"))
      (node (ref "R7") (pin "2") (pinfunction "2_2") (pintype "passive"))
      (node (ref "R8") (pin "2") (pinfunction "2_2") (pintype "passive"))
      (node (ref "VR1") (pin "A") (pinfunction "A_A") (pintype "passive"))
      (node (ref "VR2") (pin "A") (pinfunction "A_A") (pintype "passive"))
      (node (ref "VR3") (pin "A") (pinfunction "A_A") (pintype "passive"))
      (node (ref "VR4") (pin "A") (pinfunction "A_A") (pintype "passive"))
      (node (ref "VR6") (pin "A") (pinfunction "A_A") (pintype "passive"))
    )
    (net (code "25") (name "Net-(IC1-AOUT1)") (class "Default")
      (node (ref "IC1") (pin "5") (pinfunction "AOUT1_5") (pintype "bidirectional"))
      (node (ref "J1") (pin "4") (pinfunction "S_4") (pintype "passive"))
    )
    (net (code "26") (name "Net-(IC1-AOUT2)") (class "Default")
      (node (ref "IC1") (pin "7") (pinfunction "AOUT2_7") (pintype "bidirectional"))
      (node (ref "J1") (pin "3") (pinfunction "S_3") (pintype "passive"))
    )
    (net (code "27") (name "Net-(IC1-BOUT1)") (class "Default")
      (node (ref "IC1") (pin "10") (pinfunction "BOUT1_10") (pintype "bidirectional"))
      (node (ref "J1") (pin "1") (pinfunction "S_1") (pintype "passive"))
    )
    (net (code "28") (name "Net-(IC1-BOUT2)") (class "Default")
      (node (ref "IC1") (pin "8") (pinfunction "BOUT2_8") (pintype "bidirectional"))
      (node (ref "J1") (pin "2") (pinfunction "S_2") (pintype "passive"))
    )
    (net (code "29") (name "Net-(IC1-CP1)") (class "Default")
      (node (ref "C1") (pin "2") (pinfunction "2_2") (pintype "passive"))
      (node (ref "IC1") (pin "1") (pinfunction "CP1_1") (pintype "bidirectional"))
    )
    (net (code "30") (name "Net-(IC1-CP2)") (class "Default")
      (node (ref "C1") (pin "1") (pinfunction "1_1") (pintype "passive"))
      (node (ref "IC1") (pin "2") (pinfunction "CP2_2") (pintype "bidirectional"))
    )
    (net (code "31") (name "Net-(IC1-DECAY)") (class "Default")
      (node (ref "IC1") (pin "19") (pinfunction "DECAY_19") (pintype "bidirectional"))
      (node (ref "J9") (pin "2") (pinfunction "2_2") (pintype "passive"))
    )
    (net (code "32") (name "Net-(IC1-ISENA)") (class "Default")
      (node (ref "IC1") (pin "6") (pinfunction "ISENA_6") (pintype "bidirectional"))
      (node (ref "R6") (pin "1") (pinfunction "1_1") (pintype "passive"))
    )
    (net (code "33") (name "Net-(IC1-ISENB)") (class "Default")
      (node (ref "IC1") (pin "9") (pinfunction "ISENB_9") (pintype "bidirectional"))
      (node (ref "R5") (pin "1") (pinfunction "1_1") (pintype "passive"))
    )
    (net (code "34") (name "Net-(IC1-MODE0)") (class "Default")
      (node (ref "IC1") (pin "24") (pinfunction "MODE0_24") (pintype "bidirectional"))
      (node (ref "J3") (pin "2") (pinfunction "2_2") (pintype "passive"))
    )
    (net (code "35") (name "Net-(IC1-MODE1)") (class "Default")
      (node (ref "IC1") (pin "25") (pinfunction "MODE1_25") (pintype "bidirectional"))
      (node (ref "J4") (pin "2") (pinfunction "2_2") (pintype "passive"))
    )
    (net (code "36") (name "Net-(IC1-MODE2)") (class "Default")
      (node (ref "IC1") (pin "26") (pinfunction "MODE2_26") (pintype "bidirectional"))
      (node (ref "J5") (pin "2") (pinfunction "2_2") (pintype "passive"))
    )
    (net (code "37") (name "Net-(IC1-V3P3OUT)") (class "Default")
      (node (ref "C7") (pin "1") (pinfunction "1_1") (pintype "passive"))
      (node (ref "IC1") (pin "15") (pinfunction "V3P3OUT_15") (pintype "bidirectional"))
      (node (ref "R1") (pin "1") (pinfunction "1_1") (pintype "passive"))
    )
    (net (code "38") (name "Net-(IC1-VCP)") (class "Default")
      (node (ref "C2") (pin "2") (pinfunction "2_2") (pintype "passive"))
      (node (ref "IC1") (pin "3") (pinfunction "VCP_3") (pintype "bidirectional"))
    )
    (net (code "39") (name "Net-(IC1-~{FAULT})") (class "Default")
      (node (ref "IC1") (pin "18") (pinfunction "~{FAULT}_18") (pintype "bidirectional"))
      (node (ref "LED2") (pin "C") (pinfunction "C_C") (pintype "passive"))
    )
    (net (code "40") (name "Net-(IC1-~{HOME})") (class "Default")
      (node (ref "IC1") (pin "27") (pinfunction "~{HOME}_27") (pintype "bidirectional"))
      (node (ref "LED1") (pin "C") (pinfunction "C_C") (pintype "passive"))
    )
    (net (code "41") (name "Net-(IC2-AOUT1)") (class "Default")
      (node (ref "IC2") (pin "5") (pinfunction "AOUT1_5") (pintype "bidirectional"))
      (node (ref "J2") (pin "4") (pinfunction "S_4") (pintype "passive"))
    )
    (net (code "42") (name "Net-(IC2-AOUT2)") (class "Default")
      (node (ref "IC2") (pin "7") (pinfunction "AOUT2_7") (pintype "bidirectional"))
      (node (ref "J2") (pin "3") (pinfunction "S_3") (pintype "passive"))
    )
    (net (code "43") (name "Net-(IC2-BOUT1)") (class "Default")
      (node (ref "IC2") (pin "10") (pinfunction "BOUT1_10") (pintype "bidirectional"))
      (node (ref "J2") (pin "1") (pinfunction "S_1") (pintype "passive"))
    )
    (net (code "44") (name "Net-(IC2-BOUT2)") (class "Default")
      (node (ref "IC2") (pin "8") (pinfunction "BOUT2_8") (pintype "bidirectional"))
      (node (ref "J2") (pin "2") (pinfunction "S_2") (pintype "passive"))
    )
    (net (code "45") (name "Net-(IC2-CP1)") (class "Default")
      (node (ref "C4") (pin "2") (pinfunction "2_2") (pintype "passive"))
      (node (ref "IC2") (pin "1") (pinfunction "CP1_1") (pintype "bidirectional"))
    )
    (net (code "46") (name "Net-(IC2-CP2)") (class "Default")
      (node (ref "C4") (pin "1") (pinfunction "1_1") (pintype "passive"))
      (node (ref "IC2") (pin "2") (pinfunction "CP2_2") (pintype "bidirectional"))
    )
    (net (code "47") (name "Net-(IC2-DECAY)") (class "Default")
      (node (ref "IC2") (pin "19") (pinfunction "DECAY_19") (pintype "bidirectional"))
      (node (ref "J10") (pin "2") (pinfunction "2_2") (pintype "passive"))
    )
    (net (code "48") (name "Net-(IC2-ISENA)") (class "Default")
      (node (ref "IC2") (pin "6") (pinfunction "ISENA_6") (pintype "bidirectional"))
      (node (ref "R8") (pin "1") (pinfunction "1_1") (pintype "passive"))
    )
    (net (code "49") (name "Net-(IC2-ISENB)") (class "Default")
      (node (ref "IC2") (pin "9") (pinfunction "ISENB_9") (pintype "bidirectional"))
      (node (ref "R7") (pin "1") (pinfunction "1_1") (pintype "passive"))
    )
    (net (code "50") (name "Net-(IC2-MODE0)") (class "Default")
      (node (ref "IC2") (pin "24") (pinfunction "MODE0_24") (pintype "bidirectional"))
      (node (ref "J6") (pin "2") (pinfunction "2_2") (pintype "passive"))
    )
    (net (code "51") (name "Net-(IC2-MODE1)") (class "Default")
      (node (ref "IC2") (pin "25") (pinfunction "MODE1_25") (pintype "bidirectional"))
      (node (ref "J7") (pin "2") (pinfunction "2_2") (pintype "passive"))
    )
    (net (code "52") (name "Net-(IC2-MODE2)") (class "Default")
      (node (ref "IC2") (pin "26") (pinfunction "MODE2_26") (pintype "bidirectional"))
      (node (ref "J8") (pin "2") (pinfunction "2_2") (pintype "passive"))
    )
    (net (code "53") (name "Net-(IC2-V3P3OUT)") (class "Default")
      (node (ref "C8") (pin "1") (pinfunction "1_1") (pintype "passive"))
      (node (ref "IC2") (pin "15") (pinfunction "V3P3OUT_15") (pintype "bidirectional"))
      (node (ref "R2") (pin "1") (pinfunction "1_1") (pintype "passive"))
    )
    (net (code "54") (name "Net-(IC2-VCP)") (class "Default")
      (node (ref "C5") (pin "2") (pinfunction "2_2") (pintype "passive"))
      (node (ref "IC2") (pin "3") (pinfunction "VCP_3") (pintype "bidirectional"))
    )
    (net (code "55") (name "Net-(IC2-~{FAULT})") (class "Default")
      (node (ref "IC2") (pin "18") (pinfunction "~{FAULT}_18") (pintype "bidirectional"))
      (node (ref "LED4") (pin "C") (pinfunction "C_C") (pintype "passive"))
    )
    (net (code "56") (name "Net-(IC2-~{HOME})") (class "Default")
      (node (ref "IC2") (pin "27") (pinfunction "~{HOME}_27") (pintype "bidirectional"))
      (node (ref "LED3") (pin "C") (pinfunction "C_C") (pintype "passive"))
    )
    (net (code "57") (name "Net-(IC3-AOUT1)") (class "Default")
      (node (ref "IC3") (pin "5") (pinfunction "AOUT1_5") (pintype "bidirectional"))
      (node (ref "J13") (pin "4") (pinfunction "S_4") (pintype "passive"))
    )
    (net (code "58") (name "Net-(IC3-AOUT2)") (class "Default")
      (node (ref "IC3") (pin "7") (pinfunction "AOUT2_7") (pintype "bidirectional"))
      (node (ref "J13") (pin "3") (pinfunction "S_3") (pintype "passive"))
    )
    (net (code "59") (name "Net-(IC3-BOUT1)") (class "Default")
      (node (ref "IC3") (pin "10") (pinfunction "BOUT1_10") (pintype "bidirectional"))
      (node (ref "J13") (pin "1") (pinfunction "S_1") (pintype "passive"))
    )
    (net (code "60") (name "Net-(IC3-BOUT2)") (class "Default")
      (node (ref "IC3") (pin "8") (pinfunction "BOUT2_8") (pintype "bidirectional"))
      (node (ref "J13") (pin "2") (pinfunction "S_2") (pintype "passive"))
    )
    (net (code "61") (name "Net-(IC3-CP1)") (class "Default")
      (node (ref "C9") (pin "2") (pinfunction "2_2") (pintype "passive"))
      (node (ref "IC3") (pin "1") (pinfunction "CP1_1") (pintype "bidirectional"))
    )
    (net (code "62") (name "Net-(IC3-CP2)") (class "Default")
      (node (ref "C9") (pin "1") (pinfunction "1_1") (pintype "passive"))
      (node (ref "IC3") (pin "2") (pinfunction "CP2_2") (pintype "bidirectional"))
    )
    (net (code "63") (name "Net-(IC3-DECAY)") (class "Default")
      (node (ref "IC3") (pin "19") (pinfunction "DECAY_19") (pintype "bidirectional"))
      (node (ref "J21") (pin "2") (pinfunction "2_2") (pintype "passive"))
    )
    (net (code "64") (name "Net-(IC3-ISENA)") (class "Default")
      (node (ref "IC3") (pin "6") (pinfunction "ISENA_6") (pintype "bidirectional"))
      (node (ref "R18") (pin "1") (pinfunction "1_1") (pintype "passive"))
    )
    (net (code "65") (name "Net-(IC3-ISENB)") (class "Default")
      (node (ref "IC3") (pin "9") (pinfunction "ISENB_9") (pintype "bidirectional"))
      (node (ref "R17") (pin "1") (pinfunction "1_1") (pintype "passive"))
    )
    (net (code "66") (name "Net-(IC3-MODE0)") (class "Default")
      (node (ref "IC3") (pin "24") (pinfunction "MODE0_24") (pintype "bidirectional"))
      (node (ref "J15") (pin "2") (pinfunction "2_2") (pintype "passive"))
    )
    (net (code "67") (name "Net-(IC3-MODE1)") (class "Default")
      (node (ref "IC3") (pin "25") (pinfunction "MODE1_25") (pintype "bidirectional"))
      (node (ref "J16") (pin "2") (pinfunction "2_2") (pintype "passive"))
    )
    (net (code "68") (name "Net-(IC3-MODE2)") (class "Default")
      (node (ref "IC3") (pin "26") (pinfunction "MODE2_26") (pintype "bidirectional"))
      (node (ref "J17") (pin "2") (pinfunction "2_2") (pintype "passive"))
    )
    (net (code "69") (name "Net-(IC3-V3P3OUT)") (class "Default")
      (node (ref "C15") (pin "1") (pinfunction "1_1") (pintype "passive"))
      (node (ref "IC3") (pin "15") (pinfunction "V3P3OUT_15") (pintype "bidirectional"))
      (node (ref "R13") (pin "1") (pinfunction "1_1") (pintype "passive"))
    )
    (net (code "70") (name "Net-(IC3-VCP)") (class "Default")
      (node (ref "C10") (pin "2") (pinfunction "2_2") (pintype "passive"))
      (node (ref "IC3") (pin "3") (pinfunction "VCP_3") (pintype "bidirectional"))
    )
    (net (code "71") (name "Net-(IC3-~{FAULT})") (class "Default")
      (node (ref "IC3") (pin "18") (pinfunction "~{FAULT}_18") (pintype "bidirectional"))
      (node (ref "LED6") (pin "C") (pinfunction "C_C") (pintype "passive"))
    )
    (net (code "72") (name "Net-(IC3-~{HOME})") (class "Default")
      (node (ref "IC3") (pin "27") (pinfunction "~{HOME}_27") (pintype "bidirectional"))
      (node (ref "LED5") (pin "C") (pinfunction "C_C") (pintype "passive"))
    )
    (net (code "73") (name "Net-(IC4-AOUT1)") (class "Default")
      (node (ref "IC4") (pin "5") (pinfunction "AOUT1_5") (pintype "bidirectional"))
      (node (ref "J14") (pin "4") (pinfunction "S_4") (pintype "passive"))
    )
    (net (code "74") (name "Net-(IC4-AOUT2)") (class "Default")
      (node (ref "IC4") (pin "7") (pinfunction "AOUT2_7") (pintype "bidirectional"))
      (node (ref "J14") (pin "3") (pinfunction "S_3") (pintype "passive"))
    )
    (net (code "75") (name "Net-(IC4-BOUT1)") (class "Default")
      (node (ref "IC4") (pin "10") (pinfunction "BOUT1_10") (pintype "bidirectional"))
      (node (ref "J14") (pin "1") (pinfunction "S_1") (pintype "passive"))
    )
    (net (code "76") (name "Net-(IC4-BOUT2)") (class "Default")
      (node (ref "IC4") (pin "8") (pinfunction "BOUT2_8") (pintype "bidirectional"))
      (node (ref "J14") (pin "2") (pinfunction "S_2") (pintype "passive"))
    )
    (net (code "77") (name "Net-(IC4-CP1)") (class "Default")
      (node (ref "C12") (pin "2") (pinfunction "2_2") (pintype "passive"))
      (node (ref "IC4") (pin "1") (pinfunction "CP1_1") (pintype "bidirectional"))
    )
    (net (code "78") (name "Net-(IC4-CP2)") (class "Default")
      (node (ref "C12") (pin "1") (pinfunction "1_1") (pintype "passive"))
      (node (ref "IC4") (pin "2") (pinfunction "CP2_2") (pintype "bidirectional"))
    )
    (net (code "79") (name "Net-(IC4-DECAY)") (class "Default")
      (node (ref "IC4") (pin "19") (pinfunction "DECAY_19") (pintype "bidirectional"))
      (node (ref "J22") (pin "2") (pinfunction "2_2") (pintype "passive"))
    )
    (net (code "80") (name "Net-(IC4-ISENA)") (class "Default")
      (node (ref "IC4") (pin "6") (pinfunction "ISENA_6") (pintype "bidirectional"))
      (node (ref "R20") (pin "1") (pinfunction "1_1") (pintype "passive"))
    )
    (net (code "81") (name "Net-(IC4-ISENB)") (class "Default")
      (node (ref "IC4") (pin "9") (pinfunction "ISENB_9") (pintype "bidirectional"))
      (node (ref "R19") (pin "1") (pinfunction "1_1") (pintype "passive"))
    )
    (net (code "82") (name "Net-(IC4-MODE0)") (class "Default")
      (node (ref "IC4") (pin "24") (pinfunction "MODE0_24") (pintype "bidirectional"))
      (node (ref "J18") (pin "2") (pinfunction "2_2") (pintype "passive"))
    )
    (net (code "83") (name "Net-(IC4-MODE1)") (class "Default")
      (node (ref "IC4") (pin "25") (pinfunction "MODE1_25") (pintype "bidirectional"))
      (node (ref "J19") (pin "2") (pinfunction "2_2") (pintype "passive"))
    )
    (net (code "84") (name "Net-(IC4-MODE2)") (class "Default")
      (node (ref "IC4") (pin "26") (pinfunction "MODE2_26") (pintype "bidirectional"))
      (node (ref "J20") (pin "2") (pinfunction "2_2") (pintype "passive"))
    )
    (net (code "85") (name "Net-(IC4-V3P3OUT)") (class "Default")
      (node (ref "C16") (pin "1") (pinfunction "1_1") (pintype "passive"))
      (node (ref "IC4") (pin "15") (pinfunction "V3P3OUT_15") (pintype "bidirectional"))
      (node (ref "R14") (pin "1") (pinfunction "1_1") (pintype "passive"))
    )
    (net (code "86") (name "Net-(IC4-VCP)") (class "Default")
      (node (ref "C13") (pin "2") (pinfunction "2_2") (pintype "passive"))
      (node (ref "IC4") (pin "3") (pinfunction "VCP_3") (pintype "bidirectional"))
    )
    (net (code "87") (name "Net-(IC4-~{FAULT})") (class "Default")
      (node (ref "IC4") (pin "18") (pinfunction "~{FAULT}_18") (pintype "bidirectional"))
      (node (ref "LED8") (pin "C") (pinfunction "C_C") (pintype "passive"))
    )
    (net (code "88") (name "Net-(IC4-~{HOME})") (class "Default")
      (node (ref "IC4") (pin "27") (pinfunction "~{HOME}_27") (pintype "bidirectional"))
      (node (ref "LED7") (pin "C") (pinfunction "C_C") (pintype "passive"))
    )
    (net (code "89") (name "Net-(IC5-CV)") (class "Default")
      (node (ref "C17") (pin "1") (pinfunction "1_1") (pintype "passive"))
      (node (ref "IC5") (pin "5") (pinfunction "CV_5") (pintype "input"))
    )
    (net (code "90") (name "Net-(IC5-DIS)") (class "Default")
      (node (ref "IC5") (pin "7") (pinfunction "DIS_7") (pintype "input"))
      (node (ref "R25") (pin "2") (pinfunction "2_2") (pintype "passive"))
      (node (ref "VR5") (pin "A") (pinfunction "A_A") (pintype "passive"))
      (node (ref "VR5") (pin "S") (pinfunction "S_S") (pintype "passive"))
    )
    (net (code "91") (name "Net-(IC5-THR)") (class "Default")
      (node (ref "C18") (pin "1") (pinfunction "1_1") (pintype "passive"))
      (node (ref "IC5") (pin "2") (pinfunction "TR_2") (pintype "input"))
      (node (ref "IC5") (pin "6") (pinfunction "THR_6") (pintype "input"))
      (node (ref "R25") (pin "1") (pinfunction "1_1") (pintype "passive"))
    )
    (net (code "92") (name "Net-(IC6-FB)") (class "Default")
      (node (ref "C21") (pin "1") (pinfunction "1_1") (pintype "passive"))
      (node (ref "IC6") (pin "2") (pinfunction "FB_2") (pintype "bidirectional"))
      (node (ref "R26") (pin "1") (pinfunction "1_1") (pintype "passive"))
      (node (ref "R28") (pin "1") (pinfunction "1_1") (pintype "passive"))
    )
    (net (code "93") (name "Net-(IC7-AOUT1)") (class "Default")
      (node (ref "IC7") (pin "5") (pinfunction "AOUT1_5") (pintype "bidirectional"))
      (node (ref "J24") (pin "4") (pinfunction "S_4") (pintype "passive"))
    )
    (net (code "94") (name "Net-(IC7-AOUT2)") (class "Default")
      (node (ref "IC7") (pin "7") (pinfunction "AOUT2_7") (pintype "bidirectional"))
      (node (ref "J24") (pin "3") (pinfunction "S_3") (pintype "passive"))
    )
    (net (code "95") (name "Net-(IC7-BOUT1)") (class "Default")
      (node (ref "IC7") (pin "10") (pinfunction "BOUT1_10") (pintype "bidirectional"))
      (node (ref "J24") (pin "1") (pinfunction "S_1") (pintype "passive"))
    )
    (net (code "96") (name "Net-(IC7-BOUT2)") (class "Default")
      (node (ref "IC7") (pin "8") (pinfunction "BOUT2_8") (pintype "bidirectional"))
      (node (ref "J24") (pin "2") (pinfunction "S_2") (pintype "passive"))
    )
    (net (code "97") (name "Net-(IC7-CP1)") (class "Default")
      (node (ref "C23") (pin "2") (pinfunction "2_2") (pintype "passive"))
      (node (ref "IC7") (pin "1") (pinfunction "CP1_1") (pintype "bidirectional"))
    )
    (net (code "98") (name "Net-(IC7-CP2)") (class "Default")
      (node (ref "C23") (pin "1") (pinfunction "1_1") (pintype "passive"))
      (node (ref "IC7") (pin "2") (pinfunction "CP2_2") (pintype "bidirectional"))
    )
    (net (code "99") (name "Net-(IC7-DECAY)") (class "Default")
      (node (ref "IC7") (pin "19") (pinfunction "DECAY_19") (pintype "bidirectional"))
      (node (ref "J28") (pin "2") (pinfunction "2_2") (pintype "passive"))
    )
    (net (code "100") (name "Net-(IC7-ISENA)") (class "Default")
      (node (ref "IC7") (pin "6") (pinfunction "ISENA_6") (pintype "bidirectional"))
      (node (ref "R32") (pin "1") (pinfunction "1_1") (pintype "passive"))
    )
    (net (code "101") (name "Net-(IC7-ISENB)") (class "Default")
      (node (ref "IC7") (pin "9") (pinfunction "ISENB_9") (pintype "bidirectional"))
      (node (ref "R31") (pin "1") (pinfunction "1_1") (pintype "passive"))
    )
    (net (code "102") (name "Net-(IC7-MODE0)") (class "Default")
      (node (ref "IC7") (pin "24") (pinfunction "MODE0_24") (pintype "bidirectional"))
      (node (ref "J25") (pin "2") (pinfunction "2_2") (pintype "passive"))
    )
    (net (code "103") (name "Net-(IC7-MODE1)") (class "Default")
      (node (ref "IC7") (pin "25") (pinfunction "MODE1_25") (pintype "bidirectional"))
      (node (ref "J26") (pin "2") (pinfunction "2_2") (pintype "passive"))
    )
    (net (code "104") (name "Net-(IC7-MODE2)") (class "Default")
      (node (ref "IC7") (pin "26") (pinfunction "MODE2_26") (pintype "bidirectional"))
      (node (ref "J27") (pin "2") (pinfunction "2_2") (pintype "passive"))
    )
    (net (code "105") (name "Net-(IC7-V3P3OUT)") (class "Default")
      (node (ref "C26") (pin "1") (pinfunction "1_1") (pintype "passive"))
      (node (ref "IC7") (pin "15") (pinfunction "V3P3OUT_15") (pintype "bidirectional"))
      (node (ref "R29") (pin "1") (pinfunction "1_1") (pintype "passive"))
    )
    (net (code "106") (name "Net-(IC7-VCP)") (class "Default")
      (node (ref "C24") (pin "2") (pinfunction "2_2") (pintype "passive"))
      (node (ref "IC7") (pin "3") (pinfunction "VCP_3") (pintype "bidirectional"))
    )
    (net (code "107") (name "Net-(IC7-~{FAULT})") (class "Default")
      (node (ref "IC7") (pin "18") (pinfunction "~{FAULT}_18") (pintype "bidirectional"))
      (node (ref "LED11") (pin "C") (pinfunction "C_C") (pintype "passive"))
    )
    (net (code "108") (name "Net-(IC7-~{HOME})") (class "Default")
      (node (ref "IC7") (pin "27") (pinfunction "~{HOME}_27") (pintype "bidirectional"))
      (node (ref "LED10") (pin "C") (pinfunction "C_C") (pintype "passive"))
    )
    (net (code "109") (name "Net-(J23A-KL)") (class "Default")
      (node (ref "F1") (pin "1") (pinfunction "1_1") (pintype "bidirectional"))
      (node (ref "F1") (pin "2") (pinfunction "1_2") (pintype "bidirectional"))
      (node (ref "J23") (pin "1") (pinfunction "KL_1") (pintype "passive"))
    )
    (net (code "110") (name "Net-(LED1-PadA)") (class "Default")
      (node (ref "LED1") (pin "A") (pinfunction "A_A") (pintype "passive"))
      (node (ref "R9") (pin "1") (pinfunction "1_1") (pintype "passive"))
    )
    (net (code "111") (name "Net-(LED2-PadA)") (class "Default")
      (node (ref "LED2") (pin "A") (pinfunction "A_A") (pintype "passive"))
      (node (ref "R10") (pin "1") (pinfunction "1_1") (pintype "passive"))
    )
    (net (code "112") (name "Net-(LED3-PadA)") (class "Default")
      (node (ref "LED3") (pin "A") (pinfunction "A_A") (pintype "passive"))
      (node (ref "R11") (pin "1") (pinfunction "1_1") (pintype "passive"))
    )
    (net (code "113") (name "Net-(LED4-PadA)") (class "Default")
      (node (ref "LED4") (pin "A") (pinfunction "A_A") (pintype "passive"))
      (node (ref "R12") (pin "1") (pinfunction "1_1") (pintype "passive"))
    )
    (net (code "114") (name "Net-(LED5-PadA)") (class "Default")
      (node (ref "LED5") (pin "A") (pinfunction "A_A") (pintype "passive"))
      (node (ref "R21") (pin "1") (pinfunction "1_1") (pintype "passive"))
    )
    (net (code "115") (name "Net-(LED6-PadA)") (class "Default")
      (node (ref "LED6") (pin "A") (pinfunction "A_A") (pintype "passive"))
      (node (ref "R22") (pin "1") (pinfunction "1_1") (pintype "passive"))
    )
    (net (code "116") (name "Net-(LED7-PadA)") (class "Default")
      (node (ref "LED7") (pin "A") (pinfunction "A_A") (pintype "passive"))
      (node (ref "R23") (pin "1") (pinfunction "1_1") (pintype "passive"))
    )
    (net (code "117") (name "Net-(LED8-PadA)") (class "Default")
      (node (ref "LED8") (pin "A") (pinfunction "A_A") (pintype "passive"))
      (node (ref "R24") (pin "1") (pinfunction "1_1") (pintype "passive"))
    )
    (net (code "118") (name "Net-(LED9-PadA)") (class "Default")
      (node (ref "LED9") (pin "A") (pinfunction "A_A") (pintype "passive"))
      (node (ref "R27") (pin "1") (pinfunction "1_1") (pintype "passive"))
    )
    (net (code "119") (name "Net-(LED10-PadA)") (class "Default")
      (node (ref "LED10") (pin "A") (pinfunction "A_A") (pintype "passive"))
      (node (ref "R33") (pin "1") (pinfunction "1_1") (pintype "passive"))
    )
    (net (code "120") (name "Net-(LED11-PadA)") (class "Default")
      (node (ref "LED11") (pin "A") (pinfunction "A_A") (pintype "passive"))
      (node (ref "R34") (pin "1") (pinfunction "1_1") (pintype "passive"))
    )
    (net (code "121") (name "Net-(R1-Pad2)") (class "Default")
      (node (ref "R1") (pin "2") (pinfunction "2_2") (pintype "passive"))
      (node (ref "VR1") (pin "E") (pinfunction "E_E") (pintype "passive"))
    )
    (net (code "122") (name "Net-(R2-Pad2)") (class "Default")
      (node (ref "R2") (pin "2") (pinfunction "2_2") (pintype "passive"))
      (node (ref "VR2") (pin "E") (pinfunction "E_E") (pintype "passive"))
    )
    (net (code "123") (name "Net-(R13-Pad2)") (class "Default")
      (node (ref "R13") (pin "2") (pinfunction "2_2") (pintype "passive"))
      (node (ref "VR3") (pin "E") (pinfunction "E_E") (pintype "passive"))
    )
    (net (code "124") (name "Net-(R14-Pad2)") (class "Default")
      (node (ref "R14") (pin "2") (pinfunction "2_2") (pintype "passive"))
      (node (ref "VR4") (pin "E") (pinfunction "E_E") (pintype "passive"))
    )
    (net (code "125") (name "Net-(R29-Pad2)") (class "Default")
      (node (ref "R29") (pin "2") (pinfunction "2_2") (pintype "passive"))
      (node (ref "VR6") (pin "E") (pinfunction "E_E") (pintype "passive"))
    )
  )
)
